# USB_DigiVOX_Interface_V5.net
KiCad netlist of a schematic drawn in EAGLE
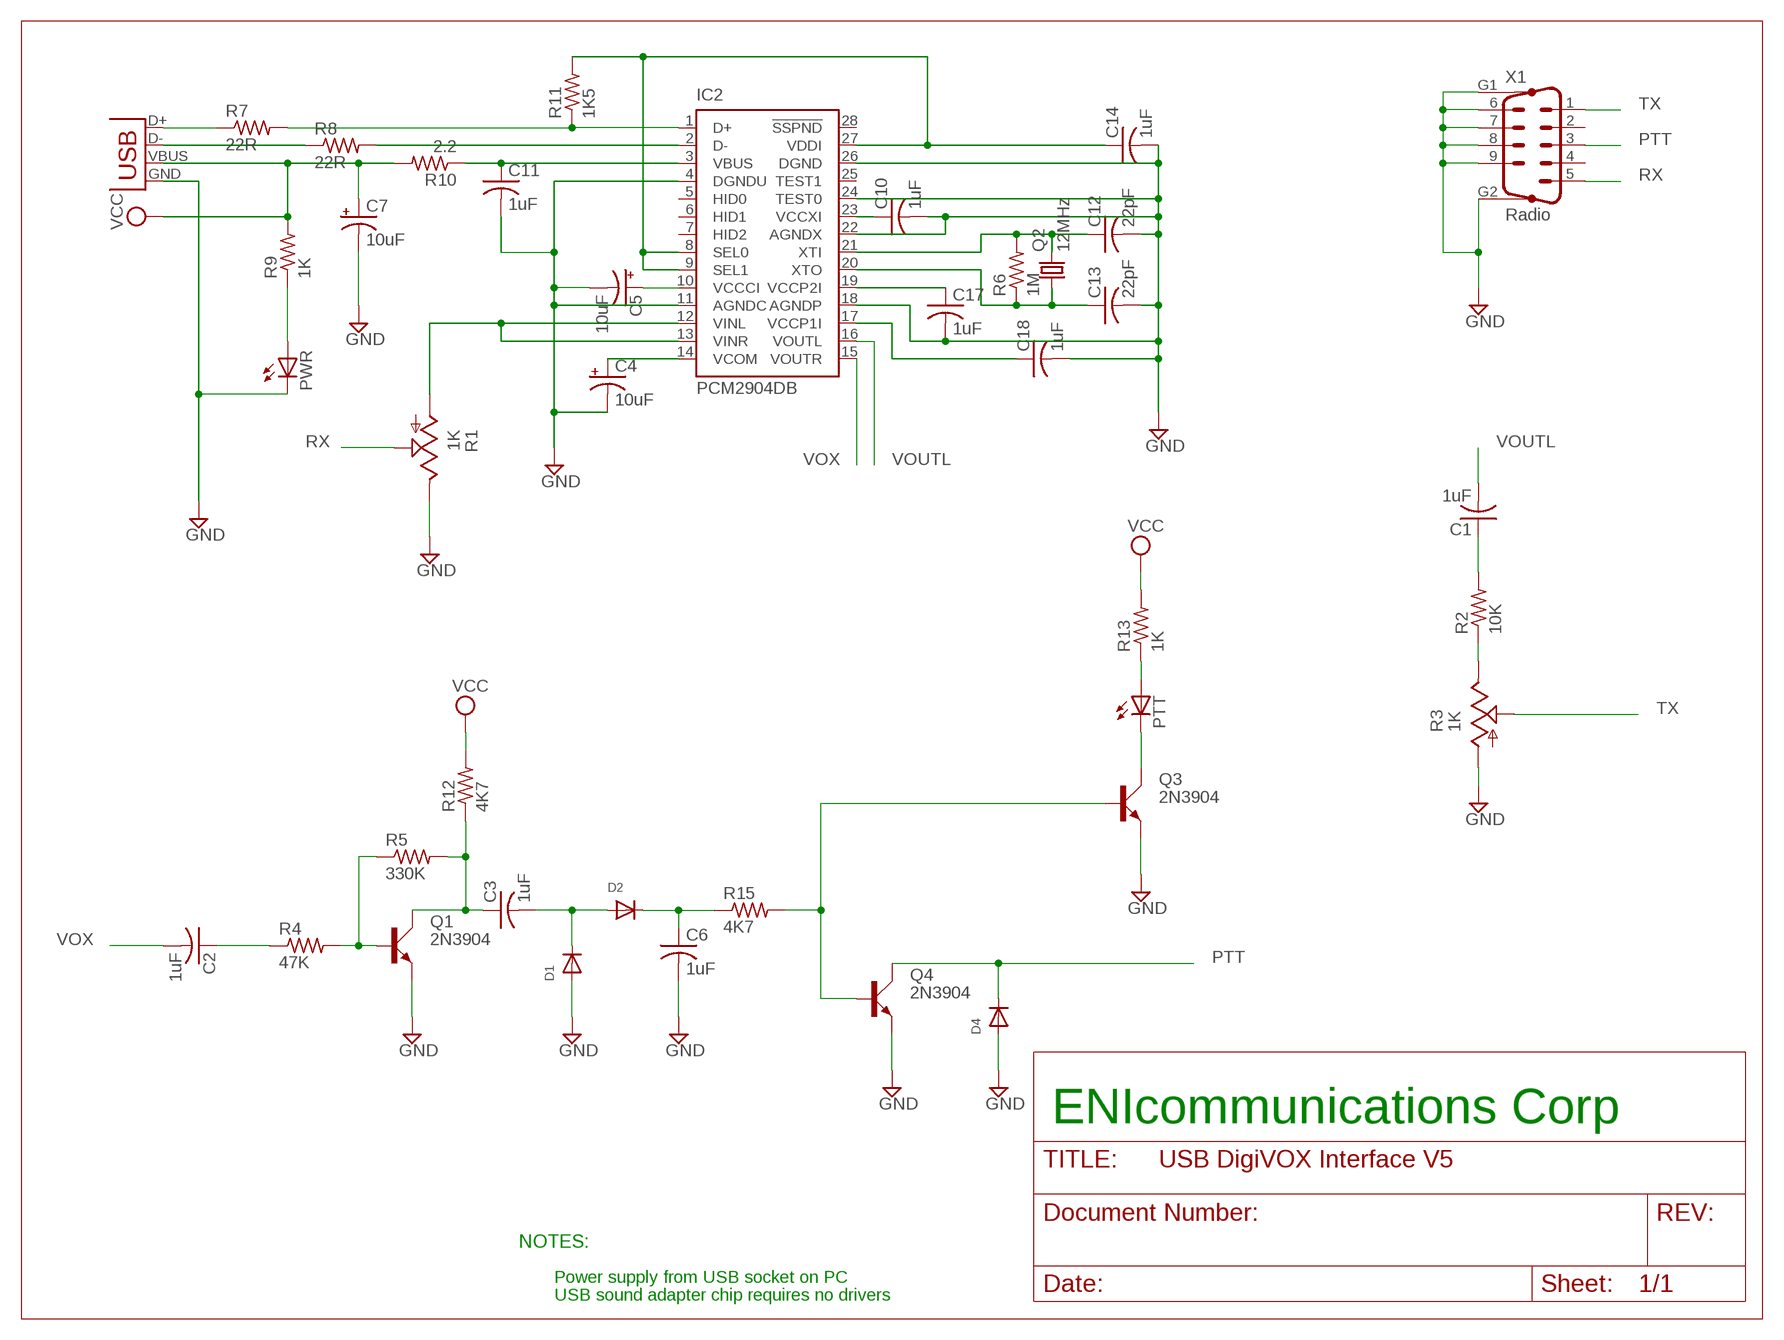
[diagram p0: schematic, sheet 1]

(export (version "E")
  (design (tool "Eeschema 10.0.6"))
  (components
    (comp (ref "C1")
      (value "1uF")
      (footprint "eagle-import:C025-025X050")
      (libsource (lib "eagle-import") (part "C-US025-025X050"))
    )
    (comp (ref "C2")
      (value "1uF")
      (footprint "eagle-import:C025-025X050")
      (libsource (lib "eagle-import") (part "C-US025-025X050"))
    )
    (comp (ref "C3")
      (value "1uF")
      (footprint "eagle-import:C025-025X050")
      (libsource (lib "eagle-import") (part "C-US025-025X050"))
    )
    (comp (ref "C4")
      (value "10uF")
      (footprint "eagle-import:CPOL-RADIAL-10UF-25V")
      (libsource (lib "eagle-import") (part "CAP_POLPTH2"))
    )
    (comp (ref "C5")
      (value "10uF")
      (footprint "eagle-import:CPOL-RADIAL-10UF-25V")
      (libsource (lib "eagle-import") (part "CAP_POLPTH2"))
    )
    (comp (ref "C6")
      (value "1uF")
      (footprint "eagle-import:C025-025X050")
      (libsource (lib "eagle-import") (part "C-US025-025X050"))
    )
    (comp (ref "C7")
      (value "10uF")
      (footprint "eagle-import:CPOL-RADIAL-10UF-25V")
      (libsource (lib "eagle-import") (part "CAP_POLPTH2"))
    )
    (comp (ref "C10")
      (value "1uF")
      (footprint "eagle-import:C025-025X050")
      (libsource (lib "eagle-import") (part "C-US025-025X050"))
    )
    (comp (ref "C11")
      (value "1uF")
      (footprint "eagle-import:C025-025X050")
      (libsource (lib "eagle-import") (part "C-US025-025X050"))
    )
    (comp (ref "C12")
      (value "22pF")
      (footprint "eagle-import:C025-025X050")
      (libsource (lib "eagle-import") (part "C-US025-025X050"))
    )
    (comp (ref "C13")
      (value "22pF")
      (footprint "eagle-import:C025-025X050")
      (libsource (lib "eagle-import") (part "C-US025-025X050"))
    )
    (comp (ref "C14")
      (value "1uF")
      (footprint "eagle-import:C025-025X050")
      (libsource (lib "eagle-import") (part "C-US025-025X050"))
    )
    (comp (ref "C17")
      (value "1uF")
      (footprint "eagle-import:C025-025X050")
      (libsource (lib "eagle-import") (part "C-US025-025X050"))
    )
    (comp (ref "C18")
      (value "1uF")
      (footprint "eagle-import:C025-025X050")
      (libsource (lib "eagle-import") (part "C-US025-025X050"))
    )
    (comp (ref "D1")
      (value "DIODEDO-1N4148")
      (footprint "eagle-import:DO-1N4148")
      (libsource (lib "eagle-import") (part "DIODEDO-1N4148"))
    )
    (comp (ref "D2")
      (value "DIODEDO-1N4148")
      (footprint "eagle-import:DO-1N4148")
      (libsource (lib "eagle-import") (part "DIODEDO-1N4148"))
    )
    (comp (ref "D4")
      (value "DIODEDO-1N4148")
      (footprint "eagle-import:DO-1N4148")
      (libsource (lib "eagle-import") (part "DIODEDO-1N4148"))
    )
    (comp (ref "IC2")
      (value "PCM2904DB")
      (footprint "eagle-import:SSOP28DB")
      (libsource (lib "eagle-import") (part "PCM2904DB"))
    )
    (comp (ref "PTT")
      (value "LED3MM")
      (footprint "eagle-import:LED3MM")
      (libsource (lib "eagle-import") (part "LED3MM"))
    )
    (comp (ref "PWR")
      (value "LED3MM")
      (footprint "eagle-import:LED3MM")
      (libsource (lib "eagle-import") (part "LED3MM"))
    )
    (comp (ref "Q1")
      (value "2N3904")
      (footprint "eagle-import:TO92D")
      (libsource (lib "eagle-import") (part "2N3904"))
    )
    (comp (ref "Q2")
      (value "12MHz")
      (footprint "eagle-import:HC49_S")
      (libsource (lib "eagle-import") (part "CRYSTALHC49S"))
    )
    (comp (ref "Q3")
      (value "2N3904")
      (footprint "eagle-import:TO92D")
      (libsource (lib "eagle-import") (part "2N3904"))
    )
    (comp (ref "Q4")
      (value "2N3904")
      (footprint "eagle-import:TO92D")
      (libsource (lib "eagle-import") (part "2N3904"))
    )
    (comp (ref "R1")
      (value "1K")
      (footprint "eagle-import:CA6V")
      (libsource (lib "eagle-import") (part "TRIM_US-CA6V"))
    )
    (comp (ref "R2")
      (value "10K")
      (footprint "eagle-import:0204_7")
      (libsource (lib "eagle-import") (part "R-US_0204/7"))
    )
    (comp (ref "R3")
      (value "1K")
      (footprint "eagle-import:CA6V")
      (libsource (lib "eagle-import") (part "TRIM_US-CA6V"))
    )
    (comp (ref "R4")
      (value "47K")
      (footprint "eagle-import:0207_2V")
      (libsource (lib "eagle-import") (part "R-US_0207/2V"))
    )
    (comp (ref "R5")
      (value "330K")
      (footprint "eagle-import:0207_2V")
      (libsource (lib "eagle-import") (part "R-US_0207/2V"))
    )
    (comp (ref "R6")
      (value "1M")
      (footprint "eagle-import:0207_2V")
      (libsource (lib "eagle-import") (part "R-US_0207/2V"))
    )
    (comp (ref "R7")
      (value "22R")
      (footprint "eagle-import:0207_2V")
      (libsource (lib "eagle-import") (part "R-US_0207/2V"))
    )
    (comp (ref "R8")
      (value "22R")
      (footprint "eagle-import:0207_2V")
      (libsource (lib "eagle-import") (part "R-US_0207/2V"))
    )
    (comp (ref "R9")
      (value "1K")
      (footprint "eagle-import:0207_2V")
      (libsource (lib "eagle-import") (part "R-US_0207/2V"))
    )
    (comp (ref "R10")
      (value "2.2")
      (footprint "eagle-import:0207_2V")
      (libsource (lib "eagle-import") (part "R-US_0207/2V"))
    )
    (comp (ref "R11")
      (value "1K5")
      (footprint "eagle-import:0207_2V")
      (libsource (lib "eagle-import") (part "R-US_0207/2V"))
    )
    (comp (ref "R12")
      (value "4K7")
      (footprint "eagle-import:0207_2V")
      (libsource (lib "eagle-import") (part "R-US_0207/2V"))
    )
    (comp (ref "R13")
      (value "1K")
      (footprint "eagle-import:0204_7")
      (libsource (lib "eagle-import") (part "R-US_0204/7"))
    )
    (comp (ref "R15")
      (value "4K7")
      (footprint "eagle-import:0207_2V")
      (libsource (lib "eagle-import") (part "R-US_0207/2V"))
    )
    (comp (ref "X1")
      (value "Radio")
      (footprint "eagle-import:M09HP")
      (libsource (lib "eagle-import") (part "M09HP"))
    )
    (comp (ref "X2")
      (value "USBSMD")
      (footprint "eagle-import:USB-MINIB")
      (libsource (lib "eagle-import") (part "USBSMD"))
    )
  )
  (nets
    (net (code "1") (name "/PTT") (class "Default")
      (node (ref "D4") (pin "C") (pinfunction "C_C") (pintype "passive"))
      (node (ref "Q4") (pin "C") (pinfunction "C_C") (pintype "passive"))
      (node (ref "X1") (pin "3") (pinfunction "3_3") (pintype "passive"))
    )
    (net (code "2") (name "/RX") (class "Default")
      (node (ref "R1") (pin "S") (pinfunction "S_S") (pintype "passive"))
      (node (ref "X1") (pin "5") (pinfunction "5_5") (pintype "passive"))
    )
    (net (code "3") (name "/TX") (class "Default")
      (node (ref "R3") (pin "S") (pinfunction "S_S") (pintype "passive"))
      (node (ref "X1") (pin "1") (pinfunction "1_1") (pintype "passive"))
    )
    (net (code "4") (name "/VOUTL") (class "Default")
      (node (ref "C1") (pin "2") (pinfunction "2_2") (pintype "passive"))
      (node (ref "IC2") (pin "16") (pinfunction "VOUTL_16") (pintype "output"))
    )
    (net (code "5") (name "/VOX") (class "Default")
      (node (ref "C2") (pin "2") (pinfunction "2_2") (pintype "passive"))
      (node (ref "IC2") (pin "15") (pinfunction "VOUTR_15") (pintype "output"))
    )
    (net (code "6") (name "GND") (class "Default")
      (node (ref "C10") (pin "2") (pinfunction "2_2") (pintype "passive"))
      (node (ref "C11") (pin "2") (pinfunction "2_2") (pintype "passive"))
      (node (ref "C12") (pin "2") (pinfunction "2_2") (pintype "passive"))
      (node (ref "C13") (pin "2") (pinfunction "2_2") (pintype "passive"))
      (node (ref "C14") (pin "2") (pinfunction "2_2") (pintype "passive"))
      (node (ref "C17") (pin "2") (pinfunction "2_2") (pintype "passive"))
      (node (ref "C18") (pin "2") (pinfunction "2_2") (pintype "passive"))
      (node (ref "C4") (pin "2") (pinfunction "-_2") (pintype "passive"))
      (node (ref "C5") (pin "2") (pinfunction "-_2") (pintype "passive"))
      (node (ref "C6") (pin "2") (pinfunction "2_2") (pintype "passive"))
      (node (ref "C7") (pin "2") (pinfunction "-_2") (pintype "passive"))
      (node (ref "D1") (pin "A") (pinfunction "A_A") (pintype "passive"))
      (node (ref "D4") (pin "A") (pinfunction "A_A") (pintype "passive"))
      (node (ref "IC2") (pin "11") (pinfunction "AGNDC_11") (pintype "power_in"))
      (node (ref "IC2") (pin "18") (pinfunction "AGNDP_18") (pintype "power_in"))
      (node (ref "IC2") (pin "22") (pinfunction "AGNDX_22") (pintype "power_in"))
      (node (ref "IC2") (pin "24") (pinfunction "TEST0_24") (pintype "input"))
      (node (ref "IC2") (pin "26") (pinfunction "DGND_26") (pintype "power_in"))
      (node (ref "IC2") (pin "4") (pinfunction "DGNDU_4") (pintype "power_in"))
      (node (ref "PWR") (pin "K") (pinfunction "C_K") (pintype "passive"))
      (node (ref "Q1") (pin "E") (pinfunction "E_E") (pintype "passive"))
      (node (ref "Q3") (pin "E") (pinfunction "E_E") (pintype "passive"))
      (node (ref "Q4") (pin "E") (pinfunction "E_E") (pintype "passive"))
      (node (ref "R1") (pin "E") (pinfunction "E_E") (pintype "passive"))
      (node (ref "R3") (pin "A") (pinfunction "A_A") (pintype "passive"))
      (node (ref "X1") (pin "6") (pinfunction "6_6") (pintype "passive"))
      (node (ref "X1") (pin "7") (pinfunction "7_7") (pintype "passive"))
      (node (ref "X1") (pin "8") (pinfunction "8_8") (pintype "passive"))
      (node (ref "X1") (pin "9") (pinfunction "9_9") (pintype "passive"))
      (node (ref "X1") (pin "G1") (pinfunction "G1_G1") (pintype "passive"))
      (node (ref "X1") (pin "G2") (pinfunction "G2_G2") (pintype "passive"))
      (node (ref "X2") (pin "GND") (pinfunction "GND_GND") (pintype "bidirectional"))
    )
    (net (code "7") (name "Net-(C1-Pad1)") (class "Default")
      (node (ref "C1") (pin "1") (pinfunction "1_1") (pintype "passive"))
      (node (ref "R2") (pin "2") (pinfunction "2_2") (pintype "passive"))
    )
    (net (code "8") (name "Net-(C2-Pad1)") (class "Default")
      (node (ref "C2") (pin "1") (pinfunction "1_1") (pintype "passive"))
      (node (ref "R4") (pin "1") (pinfunction "1_1") (pintype "passive"))
    )
    (net (code "9") (name "Net-(C3-Pad1)") (class "Default")
      (node (ref "C3") (pin "1") (pinfunction "1_1") (pintype "passive"))
      (node (ref "Q1") (pin "C") (pinfunction "C_C") (pintype "passive"))
      (node (ref "R12") (pin "1") (pinfunction "1_1") (pintype "passive"))
      (node (ref "R5") (pin "2") (pinfunction "2_2") (pintype "passive"))
    )
    (net (code "10") (name "Net-(C3-Pad2)") (class "Default")
      (node (ref "C3") (pin "2") (pinfunction "2_2") (pintype "passive"))
      (node (ref "D1") (pin "C") (pinfunction "C_C") (pintype "passive"))
      (node (ref "D2") (pin "A") (pinfunction "A_A") (pintype "passive"))
    )
    (net (code "11") (name "Net-(C4-+)") (class "Default")
      (node (ref "C4") (pin "1") (pinfunction "+_1") (pintype "passive"))
      (node (ref "IC2") (pin "14") (pinfunction "VCOM_14") (pintype "power_in"))
    )
    (net (code "12") (name "Net-(C5-+)") (class "Default")
      (node (ref "C5") (pin "1") (pinfunction "+_1") (pintype "passive"))
      (node (ref "IC2") (pin "10") (pinfunction "VCCCI_10") (pintype "power_in"))
    )
    (net (code "13") (name "Net-(C6-Pad1)") (class "Default")
      (node (ref "C6") (pin "1") (pinfunction "1_1") (pintype "passive"))
      (node (ref "D2") (pin "C") (pinfunction "C_C") (pintype "passive"))
      (node (ref "R15") (pin "1") (pinfunction "1_1") (pintype "passive"))
    )
    (net (code "14") (name "Net-(IC2-D+)") (class "Default")
      (node (ref "IC2") (pin "1") (pinfunction "D+_1") (pintype "bidirectional"))
      (node (ref "R11") (pin "1") (pinfunction "1_1") (pintype "passive"))
      (node (ref "R7") (pin "2") (pinfunction "2_2") (pintype "passive"))
    )
    (net (code "15") (name "Net-(IC2-D-)") (class "Default")
      (node (ref "IC2") (pin "2") (pinfunction "D-_2") (pintype "bidirectional"))
      (node (ref "R8") (pin "2") (pinfunction "2_2") (pintype "passive"))
    )
    (net (code "16") (name "Net-(IC2-SEL0)") (class "Default")
      (node (ref "C14") (pin "1") (pinfunction "1_1") (pintype "passive"))
      (node (ref "IC2") (pin "27") (pinfunction "VDDI_27") (pintype "power_in"))
      (node (ref "IC2") (pin "8") (pinfunction "SEL0_8") (pintype "input"))
      (node (ref "IC2") (pin "9") (pinfunction "SEL1_9") (pintype "input"))
      (node (ref "R11") (pin "2") (pinfunction "2_2") (pintype "passive"))
    )
    (net (code "17") (name "Net-(IC2-VBUS)") (class "Default")
      (node (ref "C11") (pin "1") (pinfunction "1_1") (pintype "passive"))
      (node (ref "IC2") (pin "3") (pinfunction "VBUS_3") (pintype "power_in"))
      (node (ref "R10") (pin "1") (pinfunction "1_1") (pintype "passive"))
    )
    (net (code "18") (name "Net-(IC2-VCCP1I)") (class "Default")
      (node (ref "C18") (pin "1") (pinfunction "1_1") (pintype "passive"))
      (node (ref "IC2") (pin "17") (pinfunction "VCCP1I_17") (pintype "input"))
    )
    (net (code "19") (name "Net-(IC2-VCCP2I)") (class "Default")
      (node (ref "C17") (pin "1") (pinfunction "1_1") (pintype "passive"))
      (node (ref "IC2") (pin "19") (pinfunction "VCCP2I_19") (pintype "power_in"))
    )
    (net (code "20") (name "Net-(IC2-VCCXI)") (class "Default")
      (node (ref "C10") (pin "1") (pinfunction "1_1") (pintype "passive"))
      (node (ref "IC2") (pin "23") (pinfunction "VCCXI_23") (pintype "power_in"))
    )
    (net (code "21") (name "Net-(IC2-VINL)") (class "Default")
      (node (ref "IC2") (pin "12") (pinfunction "VINL_12") (pintype "input"))
      (node (ref "IC2") (pin "13") (pinfunction "VINR_13") (pintype "input"))
      (node (ref "R1") (pin "A") (pinfunction "A_A") (pintype "passive"))
    )
    (net (code "22") (name "Net-(IC2-XTI)") (class "Default")
      (node (ref "C12") (pin "1") (pinfunction "1_1") (pintype "passive"))
      (node (ref "IC2") (pin "21") (pinfunction "XTI_21") (pintype "input"))
      (node (ref "Q2") (pin "2") (pinfunction "2_2") (pintype "passive"))
      (node (ref "R6") (pin "2") (pinfunction "2_2") (pintype "passive"))
    )
    (net (code "23") (name "Net-(IC2-XTO)") (class "Default")
      (node (ref "C13") (pin "1") (pinfunction "1_1") (pintype "passive"))
      (node (ref "IC2") (pin "20") (pinfunction "XTO_20") (pintype "output"))
      (node (ref "Q2") (pin "1") (pinfunction "1_1") (pintype "passive"))
      (node (ref "R6") (pin "1") (pinfunction "1_1") (pintype "passive"))
    )
    (net (code "24") (name "Net-(PTT-C)") (class "Default")
      (node (ref "PTT") (pin "K") (pinfunction "C_K") (pintype "passive"))
      (node (ref "Q3") (pin "C") (pinfunction "C_C") (pintype "passive"))
    )
    (net (code "25") (name "Net-(PTT-PadA)") (class "Default")
      (node (ref "PTT") (pin "A") (pinfunction "A_A") (pintype "passive"))
      (node (ref "R13") (pin "1") (pinfunction "1_1") (pintype "passive"))
    )
    (net (code "26") (name "Net-(PWR-PadA)") (class "Default")
      (node (ref "PWR") (pin "A") (pinfunction "A_A") (pintype "passive"))
      (node (ref "R9") (pin "1") (pinfunction "1_1") (pintype "passive"))
    )
    (net (code "27") (name "Net-(Q1-PadB)") (class "Default")
      (node (ref "Q1") (pin "B") (pinfunction "B_B") (pintype "passive"))
      (node (ref "R4") (pin "2") (pinfunction "2_2") (pintype "passive"))
      (node (ref "R5") (pin "1") (pinfunction "1_1") (pintype "passive"))
    )
    (net (code "28") (name "Net-(Q3-PadB)") (class "Default")
      (node (ref "Q3") (pin "B") (pinfunction "B_B") (pintype "passive"))
      (node (ref "Q4") (pin "B") (pinfunction "B_B") (pintype "passive"))
      (node (ref "R15") (pin "2") (pinfunction "2_2") (pintype "passive"))
    )
    (net (code "29") (name "Net-(R2-Pad1)") (class "Default")
      (node (ref "R2") (pin "1") (pinfunction "1_1") (pintype "passive"))
      (node (ref "R3") (pin "E") (pinfunction "E_E") (pintype "passive"))
    )
    (net (code "30") (name "Net-(R7-Pad1)") (class "Default")
      (node (ref "R7") (pin "1") (pinfunction "1_1") (pintype "passive"))
      (node (ref "X2") (pin "D+") (pinfunction "D+_D+") (pintype "bidirectional"))
    )
    (net (code "31") (name "Net-(R8-Pad1)") (class "Default")
      (node (ref "R8") (pin "1") (pinfunction "1_1") (pintype "passive"))
      (node (ref "X2") (pin "D-") (pinfunction "D-_D-") (pintype "bidirectional"))
    )
    (net (code "32") (name "VCC") (class "Default")
      (node (ref "C7") (pin "1") (pinfunction "+_1") (pintype "passive"))
      (node (ref "R10") (pin "2") (pinfunction "2_2") (pintype "passive"))
      (node (ref "R12") (pin "2") (pinfunction "2_2") (pintype "passive"))
      (node (ref "R13") (pin "2") (pinfunction "2_2") (pintype "passive"))
      (node (ref "R9") (pin "2") (pinfunction "2_2") (pintype "passive"))
      (node (ref "X2") (pin "VBUS") (pinfunction "VBUS_VBUS") (pintype "bidirectional"))
    )
    (net (code "33") (name "unconnected-(IC2-HID0-Pad5)") (class "Default")
      (node (ref "IC2") (pin "5") (pinfunction "HID0_5") (pintype "input"))
    )
    (net (code "34") (name "unconnected-(IC2-HID1-Pad6)") (class "Default")
      (node (ref "IC2") (pin "6") (pinfunction "HID1_6") (pintype "input"))
    )
    (net (code "35") (name "unconnected-(IC2-HID2-Pad7)") (class "Default")
      (node (ref "IC2") (pin "7") (pinfunction "HID2_7") (pintype "input"))
    )
    (net (code "36") (name "unconnected-(IC2-TEST1-Pad25)") (class "Default")
      (node (ref "IC2") (pin "25") (pinfunction "TEST1_25") (pintype "output"))
    )
    (net (code "37") (name "unconnected-(IC2-~{SSPND}-Pad28)") (class "Default")
      (node (ref "IC2") (pin "28") (pinfunction "~{SSPND}_28") (pintype "output"))
    )
    (net (code "38") (name "unconnected-(X1-Pad2)") (class "Default")
      (node (ref "X1") (pin "2") (pinfunction "2_2") (pintype "passive"))
    )
    (net (code "39") (name "unconnected-(X1-Pad4)") (class "Default")
      (node (ref "X1") (pin "4") (pinfunction "4_4") (pintype "passive"))
    )
  )
)
